# Analog_-_High_Speed_DE.net
KiCad netlist of a schematic drawn in Altium Designer
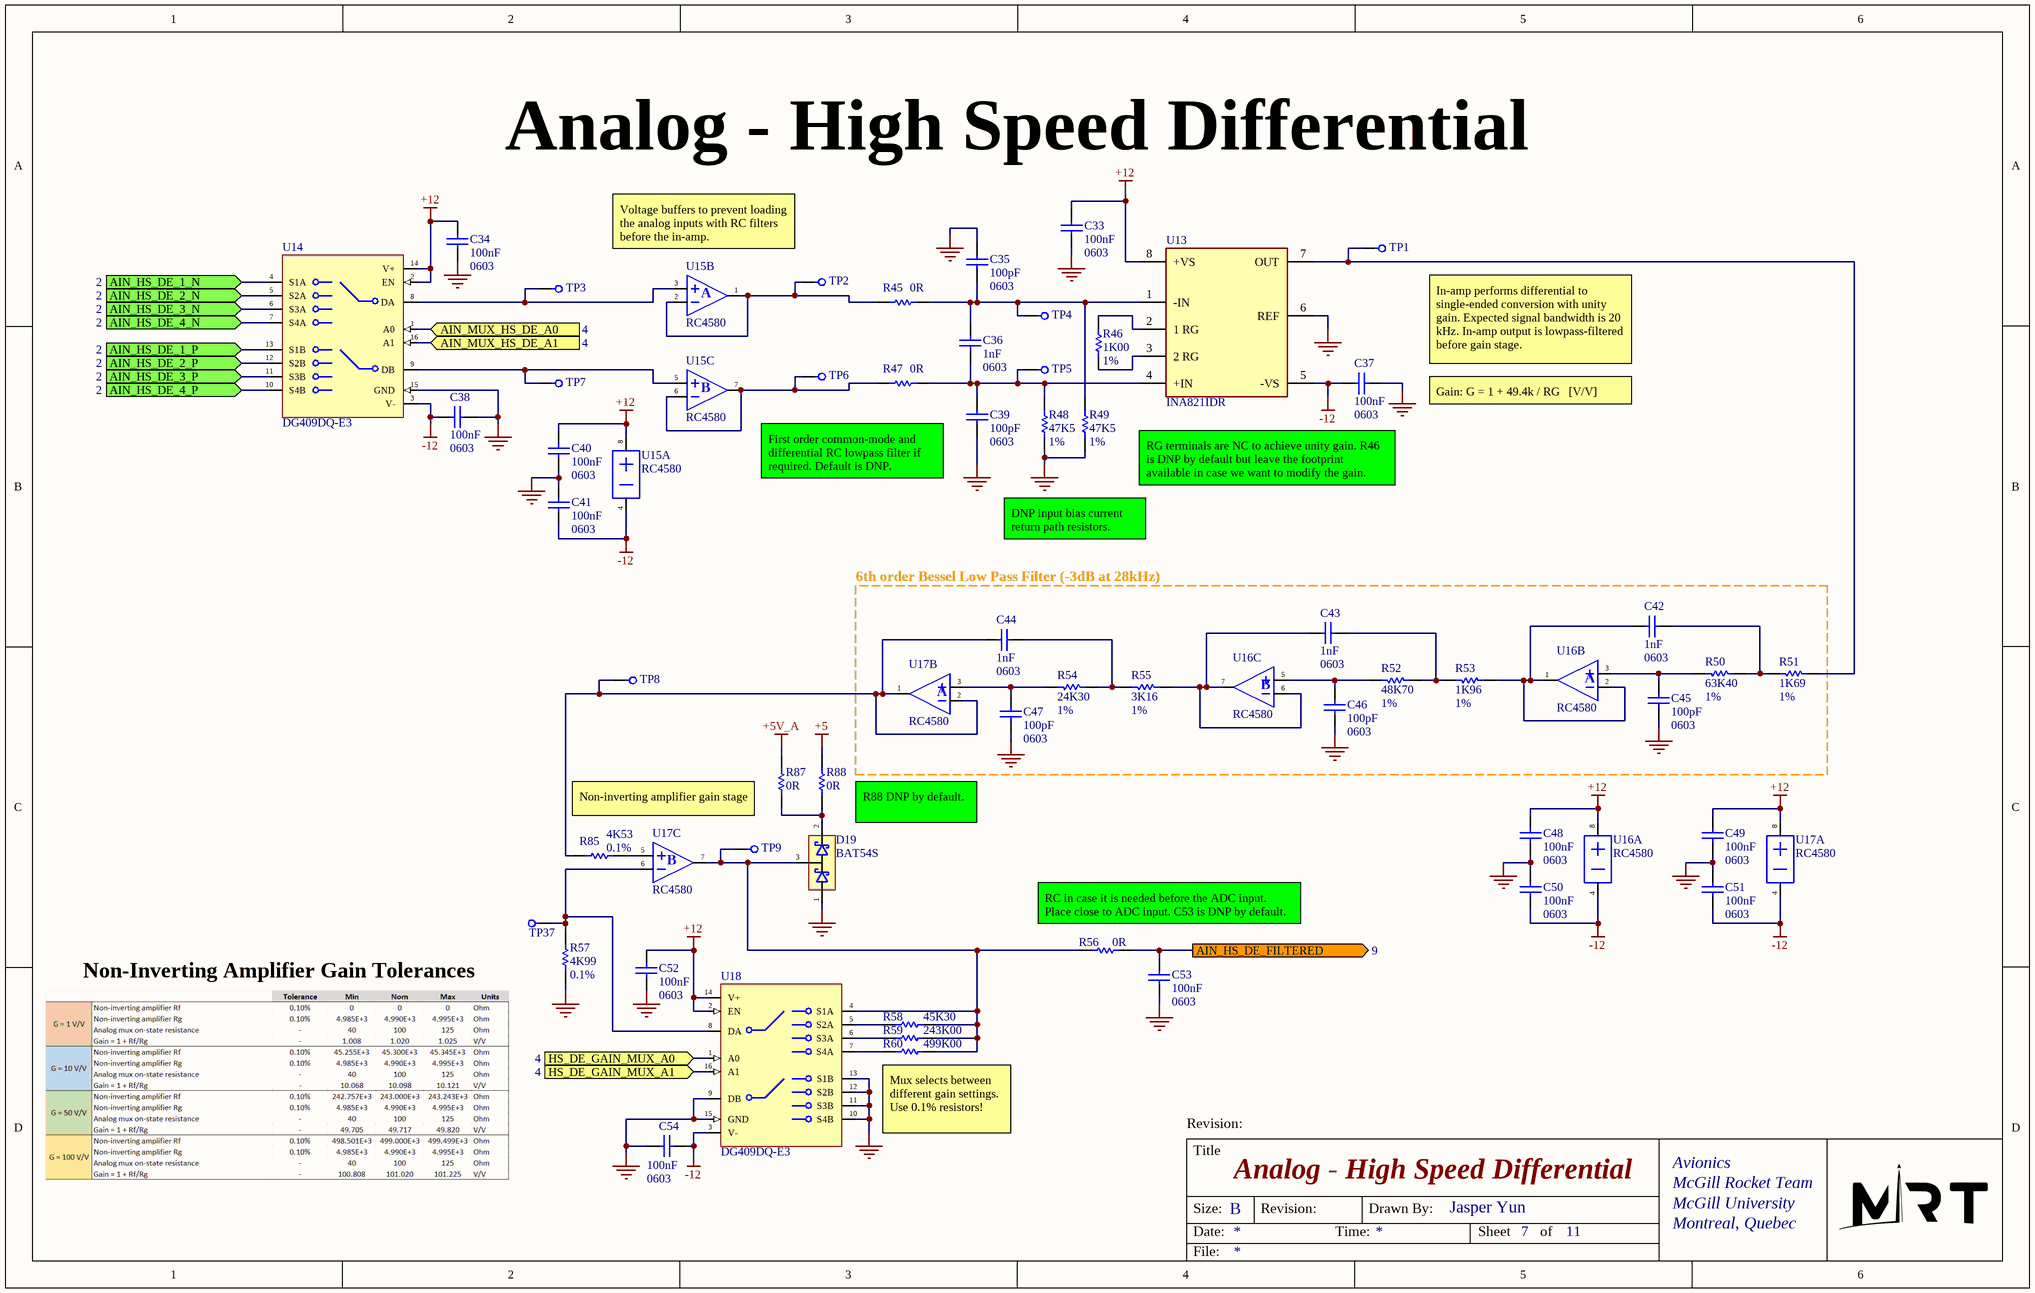
[diagram p0: Analog - High Speed DE.SchDoc]

(export (version "E")
  (design (tool "Eeschema 10.0.6"))
  (components
    (comp (ref "C33")
      (value "100nF")
      (footprint "0603 CAP SAMSUNG CL10C")
      (description "Capacitor")
      (fields (field (name "ALTIUM_VALUE") "0603") (field (name "PUBLISHER") "Altium Limited"))
      (libsource (lib "Miscellaneous Devices") (part "Cap"))
    )
    (comp (ref "C34")
      (value "100nF")
      (footprint "0603 CAP SAMSUNG CL10C")
      (description "Capacitor")
      (fields (field (name "ALTIUM_VALUE") "0603") (field (name "PUBLISHER") "Altium Limited"))
      (libsource (lib "Miscellaneous Devices") (part "Cap"))
    )
    (comp (ref "C35")
      (value "100pF")
      (footprint "0603 CAP SAMSUNG CL10C")
      (description "Capacitor")
      (fields (field (name "ALTIUM_VALUE") "0603") (field (name "PUBLISHER") "Altium Limited"))
      (libsource (lib "Miscellaneous Devices") (part "Cap"))
    )
    (comp (ref "C36")
      (value "1nF")
      (footprint "0603 CAP SAMSUNG CL10C")
      (description "Capacitor")
      (fields (field (name "ALTIUM_VALUE") "0603") (field (name "PUBLISHER") "Altium Limited"))
      (libsource (lib "Miscellaneous Devices") (part "Cap"))
    )
    (comp (ref "C37")
      (value "100nF")
      (footprint "0603 CAP SAMSUNG CL10C")
      (description "Capacitor")
      (fields (field (name "ALTIUM_VALUE") "0603") (field (name "PUBLISHER") "Altium Limited"))
      (libsource (lib "Miscellaneous Devices") (part "Cap"))
    )
    (comp (ref "C38")
      (value "100nF")
      (footprint "0603 CAP SAMSUNG CL10C")
      (description "Capacitor")
      (fields (field (name "ALTIUM_VALUE") "0603") (field (name "PUBLISHER") "Altium Limited"))
      (libsource (lib "Miscellaneous Devices") (part "Cap"))
    )
    (comp (ref "C39")
      (value "100pF")
      (footprint "0603 CAP SAMSUNG CL10C")
      (description "Capacitor")
      (fields (field (name "ALTIUM_VALUE") "0603") (field (name "PUBLISHER") "Altium Limited"))
      (libsource (lib "Miscellaneous Devices") (part "Cap"))
    )
    (comp (ref "C40")
      (value "100nF")
      (footprint "0603 CAP SAMSUNG CL10C")
      (description "Capacitor")
      (fields (field (name "ALTIUM_VALUE") "0603") (field (name "PUBLISHER") "Altium Limited"))
      (libsource (lib "Miscellaneous Devices") (part "Cap"))
    )
    (comp (ref "C41")
      (value "100nF")
      (footprint "0603 CAP SAMSUNG CL10C")
      (description "Capacitor")
      (fields (field (name "ALTIUM_VALUE") "0603") (field (name "PUBLISHER") "Altium Limited"))
      (libsource (lib "Miscellaneous Devices") (part "Cap"))
    )
    (comp (ref "C42")
      (value "1nF")
      (footprint "0603 CAP SAMSUNG CL10C")
      (description "Capacitor")
      (fields (field (name "ALTIUM_VALUE") "0603") (field (name "PUBLISHER") "Altium Limited"))
      (libsource (lib "Miscellaneous Devices") (part "Cap"))
    )
    (comp (ref "C43")
      (value "1nF")
      (footprint "0603 CAP SAMSUNG CL10C")
      (description "Capacitor")
      (fields (field (name "ALTIUM_VALUE") "0603") (field (name "PUBLISHER") "Altium Limited"))
      (libsource (lib "Miscellaneous Devices") (part "Cap"))
    )
    (comp (ref "C44")
      (value "1nF")
      (footprint "0603 CAP SAMSUNG CL10C")
      (description "Capacitor")
      (fields (field (name "ALTIUM_VALUE") "0603") (field (name "PUBLISHER") "Altium Limited"))
      (libsource (lib "Miscellaneous Devices") (part "Cap"))
    )
    (comp (ref "C45")
      (value "100pF")
      (footprint "0603 CAP SAMSUNG CL10C")
      (description "Capacitor")
      (fields (field (name "ALTIUM_VALUE") "0603") (field (name "PUBLISHER") "Altium Limited"))
      (libsource (lib "Miscellaneous Devices") (part "Cap"))
    )
    (comp (ref "C46")
      (value "100pF")
      (footprint "0603 CAP SAMSUNG CL10C")
      (description "Capacitor")
      (fields (field (name "ALTIUM_VALUE") "0603") (field (name "PUBLISHER") "Altium Limited"))
      (libsource (lib "Miscellaneous Devices") (part "Cap"))
    )
    (comp (ref "C47")
      (value "100pF")
      (footprint "0603 CAP SAMSUNG CL10C")
      (description "Capacitor")
      (fields (field (name "ALTIUM_VALUE") "0603") (field (name "PUBLISHER") "Altium Limited"))
      (libsource (lib "Miscellaneous Devices") (part "Cap"))
    )
    (comp (ref "C48")
      (value "100nF")
      (footprint "0603 CAP SAMSUNG CL10C")
      (description "Capacitor")
      (fields (field (name "ALTIUM_VALUE") "0603") (field (name "PUBLISHER") "Altium Limited"))
      (libsource (lib "Miscellaneous Devices") (part "Cap"))
    )
    (comp (ref "C49")
      (value "100nF")
      (footprint "0603 CAP SAMSUNG CL10C")
      (description "Capacitor")
      (fields (field (name "ALTIUM_VALUE") "0603") (field (name "PUBLISHER") "Altium Limited"))
      (libsource (lib "Miscellaneous Devices") (part "Cap"))
    )
    (comp (ref "C50")
      (value "100nF")
      (footprint "0603 CAP SAMSUNG CL10C")
      (description "Capacitor")
      (fields (field (name "ALTIUM_VALUE") "0603") (field (name "PUBLISHER") "Altium Limited"))
      (libsource (lib "Miscellaneous Devices") (part "Cap"))
    )
    (comp (ref "C51")
      (value "100nF")
      (footprint "0603 CAP SAMSUNG CL10C")
      (description "Capacitor")
      (fields (field (name "ALTIUM_VALUE") "0603") (field (name "PUBLISHER") "Altium Limited"))
      (libsource (lib "Miscellaneous Devices") (part "Cap"))
    )
    (comp (ref "C52")
      (value "100nF")
      (footprint "0603 CAP SAMSUNG CL10C")
      (description "Capacitor")
      (fields (field (name "ALTIUM_VALUE") "0603") (field (name "PUBLISHER") "Altium Limited"))
      (libsource (lib "Miscellaneous Devices") (part "Cap"))
    )
    (comp (ref "C53")
      (value "100nF")
      (footprint "0603 CAP SAMSUNG CL10C")
      (description "Capacitor")
      (fields (field (name "ALTIUM_VALUE") "0603") (field (name "PUBLISHER") "Altium Limited"))
      (libsource (lib "Miscellaneous Devices") (part "Cap"))
    )
    (comp (ref "C54")
      (value "100nF")
      (footprint "0603 CAP SAMSUNG CL10C")
      (description "Capacitor")
      (fields (field (name "ALTIUM_VALUE") "0603") (field (name "PUBLISHER") "Altium Limited"))
      (libsource (lib "Miscellaneous Devices") (part "Cap"))
    )
    (comp (ref "D19")
      (value "BAT54S")
      (footprint "SOT23-3")
      (description "Rectifier Diode Small Signal Schottky 40V 0.3A 5ns 3-Pin SOT-23 T/R")
      (fields
        (field (name "MANUFACTURER") "STMicroelectronics")
        (field (name "MANUFACTURER PART NUMBER") "BAT54SFILM")
      )
      (libsource (lib "MRT SCH Library") (part "Schottky Diode Array BAT54S"))
    )
    (comp (ref "R45")
      (value "0R")
      (footprint "0603 RES")
      (description "Resistor")
      (fields (field (name "PUBLISHER") "Altium Limited"))
      (libsource (lib "Miscellaneous Devices") (part "Res1"))
    )
    (comp (ref "R46")
      (value "1K00")
      (footprint "0603 RES")
      (description "Resistor")
      (fields (field (name "ALTIUM_VALUE") "1%") (field (name "PUBLISHER") "Altium Limited"))
      (libsource (lib "Miscellaneous Devices") (part "Res1"))
    )
    (comp (ref "R47")
      (value "0R")
      (footprint "0603 RES")
      (description "Resistor")
      (fields (field (name "PUBLISHER") "Altium Limited"))
      (libsource (lib "Miscellaneous Devices") (part "Res1"))
    )
    (comp (ref "R48")
      (value "47K5")
      (footprint "0603 RES")
      (description "Resistor")
      (fields (field (name "ALTIUM_VALUE") "1%") (field (name "PUBLISHER") "Altium Limited"))
      (libsource (lib "Miscellaneous Devices") (part "Res1"))
    )
    (comp (ref "R49")
      (value "47K5")
      (footprint "0603 RES")
      (description "Resistor")
      (fields (field (name "ALTIUM_VALUE") "1%") (field (name "PUBLISHER") "Altium Limited"))
      (libsource (lib "Miscellaneous Devices") (part "Res1"))
    )
    (comp (ref "R50")
      (value "63K40")
      (footprint "0603 RES")
      (description "Resistor")
      (fields (field (name "ALTIUM_VALUE") "1%") (field (name "PUBLISHER") "Altium Limited"))
      (libsource (lib "Miscellaneous Devices") (part "Res1"))
    )
    (comp (ref "R51")
      (value "1K69")
      (footprint "0603 RES")
      (description "Resistor")
      (fields (field (name "ALTIUM_VALUE") "1%") (field (name "PUBLISHER") "Altium Limited"))
      (libsource (lib "Miscellaneous Devices") (part "Res1"))
    )
    (comp (ref "R52")
      (value "48K70")
      (footprint "0603 RES")
      (description "Resistor")
      (fields (field (name "ALTIUM_VALUE") "1%") (field (name "PUBLISHER") "Altium Limited"))
      (libsource (lib "Miscellaneous Devices") (part "Res1"))
    )
    (comp (ref "R53")
      (value "1K96")
      (footprint "0603 RES")
      (description "Resistor")
      (fields (field (name "ALTIUM_VALUE") "1%") (field (name "PUBLISHER") "Altium Limited"))
      (libsource (lib "Miscellaneous Devices") (part "Res1"))
    )
    (comp (ref "R54")
      (value "24K30")
      (footprint "0603 RES")
      (description "Resistor")
      (fields (field (name "ALTIUM_VALUE") "1%") (field (name "PUBLISHER") "Altium Limited"))
      (libsource (lib "Miscellaneous Devices") (part "Res1"))
    )
    (comp (ref "R55")
      (value "3K16")
      (footprint "0603 RES")
      (description "Resistor")
      (fields (field (name "ALTIUM_VALUE") "1%") (field (name "PUBLISHER") "Altium Limited"))
      (libsource (lib "Miscellaneous Devices") (part "Res1"))
    )
    (comp (ref "R56")
      (value "0R")
      (footprint "0603 RES")
      (description "Resistor")
      (fields (field (name "PUBLISHER") "Altium Limited"))
      (libsource (lib "Miscellaneous Devices") (part "Res1"))
    )
    (comp (ref "R57")
      (value "4K99")
      (footprint "0603 RES")
      (description "Resistor")
      (fields (field (name "ALTIUM_VALUE") "0.1%") (field (name "PUBLISHER") "Altium Limited"))
      (libsource (lib "Miscellaneous Devices") (part "Res1"))
    )
    (comp (ref "R58")
      (value "45K30")
      (footprint "0603 RES")
      (description "Resistor")
      (fields (field (name "PUBLISHER") "Altium Limited"))
      (libsource (lib "Miscellaneous Devices") (part "Res1"))
    )
    (comp (ref "R59")
      (value "243K00")
      (footprint "0603 RES")
      (description "Resistor")
      (fields (field (name "PUBLISHER") "Altium Limited"))
      (libsource (lib "Miscellaneous Devices") (part "Res1"))
    )
    (comp (ref "R60")
      (value "499K00")
      (footprint "0603 RES")
      (description "Resistor")
      (fields (field (name "PUBLISHER") "Altium Limited"))
      (libsource (lib "Miscellaneous Devices") (part "Res1"))
    )
    (comp (ref "R85")
      (value "4K53")
      (footprint "0603 RES")
      (description "Resistor")
      (fields (field (name "ALTIUM_VALUE") "0.1%") (field (name "PUBLISHER") "Altium Limited"))
      (libsource (lib "Miscellaneous Devices") (part "Res1"))
    )
    (comp (ref "R87")
      (value "0R")
      (footprint "0603 RES")
      (description "Resistor")
      (fields (field (name "PUBLISHER") "Altium Limited"))
      (libsource (lib "Miscellaneous Devices") (part "Res1"))
    )
    (comp (ref "R88")
      (value "0R")
      (footprint "0603 RES")
      (description "Resistor")
      (fields (field (name "PUBLISHER") "Altium Limited"))
      (libsource (lib "Miscellaneous Devices") (part "Res1"))
    )
    (comp (ref "TP1")
      (value "Test Point")
      (footprint "Test Point Keystone 5015")
      (description "Keystone 5015 Test point")
      (libsource (lib "MRT SCH Library") (part "Test Point"))
    )
    (comp (ref "TP2")
      (value "Test Point")
      (footprint "TEST POINT SMD PAD")
      (description "Keystone 5015 Test point")
      (libsource (lib "MRT SCH Library") (part "Test Point"))
    )
    (comp (ref "TP3")
      (value "Test Point")
      (footprint "TEST POINT SMD PAD")
      (description "Keystone 5015 Test point")
      (libsource (lib "MRT SCH Library") (part "Test Point"))
    )
    (comp (ref "TP4")
      (value "Test Point")
      (footprint "TEST POINT SMD PAD")
      (description "Keystone 5015 Test point")
      (libsource (lib "MRT SCH Library") (part "Test Point"))
    )
    (comp (ref "TP5")
      (value "Test Point")
      (footprint "TEST POINT SMD PAD")
      (description "Keystone 5015 Test point")
      (libsource (lib "MRT SCH Library") (part "Test Point"))
    )
    (comp (ref "TP6")
      (value "Test Point")
      (footprint "TEST POINT SMD PAD")
      (description "Keystone 5015 Test point")
      (libsource (lib "MRT SCH Library") (part "Test Point"))
    )
    (comp (ref "TP7")
      (value "Test Point")
      (footprint "TEST POINT SMD PAD")
      (description "Keystone 5015 Test point")
      (libsource (lib "MRT SCH Library") (part "Test Point"))
    )
    (comp (ref "TP8")
      (value "Test Point")
      (footprint "Test Point Keystone 5015")
      (description "Keystone 5015 Test point")
      (libsource (lib "MRT SCH Library") (part "Test Point"))
    )
    (comp (ref "TP9")
      (value "Test Point")
      (footprint "Test Point Keystone 5015")
      (description "Keystone 5015 Test point")
      (libsource (lib "MRT SCH Library") (part "Test Point"))
    )
    (comp (ref "TP37")
      (value "Test Point")
      (footprint "Test Point Keystone 5015")
      (description "Keystone 5015 Test point")
      (libsource (lib "MRT SCH Library") (part "Test Point"))
    )
    (comp (ref "U13")
      (value "INA821IDR")
      (footprint "FP-D0008A-IPC_A")
      (description "IC INST AMP 1 CIRCUIT 8SOIC")
      (libsource (lib "Altium Content Vault") (part "f8dea4e880bbf27f1efc339ce0e0823"))
    )
    (comp (ref "U14")
      (value "DG409DQ-E3")
      (footprint "TSSOP-16")
      (description "DG409 Series 20 V 8-Ch/Dual 4-Ch High-Performance CMOS Analog Multiplexer")
      (fields (field (name "MANUFACTURER") "Vishay Siliconix"))
      (libsource (lib "") (part "Analog Mux DG409DQ-E3_1"))
    )
    (comp (ref "U15")
      (value "RC4580")
      (footprint "SOIC-8")
      (fields
        (field (name "MANUFACTURER") "Texas Instruments")
        (field (name "MANUFACTURER PART NUMBER") "RC4580IDR")
      )
      (libsource (lib "MRT SCH Library") (part "OP AMP RC4580"))
    )
    (comp (ref "U16")
      (value "RC4580")
      (footprint "SOIC-8")
      (fields
        (field (name "MANUFACTURER") "Texas Instruments")
        (field (name "MANUFACTURER PART NUMBER") "RC4580IDR")
      )
      (libsource (lib "MRT SCH Library") (part "OP AMP RC4580"))
    )
    (comp (ref "U17")
      (value "RC4580")
      (footprint "SOIC-8")
      (fields
        (field (name "MANUFACTURER") "Texas Instruments")
        (field (name "MANUFACTURER PART NUMBER") "RC4580IDR")
      )
      (libsource (lib "MRT SCH Library") (part "OP AMP RC4580"))
    )
    (comp (ref "U18")
      (value "DG409DQ-E3")
      (footprint "TSSOP-16")
      (description "DG409 Series 20 V 8-Ch/Dual 4-Ch High-Performance CMOS Analog Multiplexer")
      (fields (field (name "MANUFACTURER") "Vishay Siliconix"))
      (libsource (lib "MRT SCH Library") (part "Analog Mux DG409DQ-E3"))
    )
  )
  (nets
    (net (code "1") (name "+5") (class "Default")
      (node (ref "R88") (pin "1") (pinfunction "1_1") (pintype "passive"))
    )
    (net (code "2") (name "+5V_A") (class "Default")
      (node (ref "R87") (pin "1") (pinfunction "1_1") (pintype "passive"))
    )
    (net (code "3") (name "+12") (class "Default")
      (node (ref "C33") (pin "2") (pinfunction "2_2") (pintype "passive"))
      (node (ref "C34") (pin "2") (pinfunction "2_2") (pintype "passive"))
      (node (ref "C40") (pin "2") (pinfunction "2_2") (pintype "passive"))
      (node (ref "C48") (pin "2") (pinfunction "2_2") (pintype "passive"))
      (node (ref "C49") (pin "2") (pinfunction "2_2") (pintype "passive"))
      (node (ref "C52") (pin "2") (pinfunction "2_2") (pintype "passive"))
      (node (ref "U13") (pin "8") (pinfunction "+VS_8") (pintype "power_in"))
      (node (ref "U14") (pin "14") (pinfunction "V+_14") (pintype "passive"))
      (node (ref "U14") (pin "2") (pinfunction "EN_2") (pintype "input"))
      (node (ref "U15") (pin "8") (pinfunction "VCC+_8") (pintype "passive"))
      (node (ref "U16") (pin "8") (pinfunction "VCC+_8") (pintype "passive"))
      (node (ref "U17") (pin "8") (pinfunction "VCC+_8") (pintype "passive"))
      (node (ref "U18") (pin "14") (pinfunction "V+_14") (pintype "passive"))
      (node (ref "U18") (pin "2") (pinfunction "EN_2") (pintype "input"))
    )
    (net (code "4") (name "-12") (class "Default")
      (node (ref "C37") (pin "2") (pinfunction "2_2") (pintype "passive"))
      (node (ref "C38") (pin "2") (pinfunction "2_2") (pintype "passive"))
      (node (ref "C41") (pin "1") (pinfunction "1_1") (pintype "passive"))
      (node (ref "C50") (pin "1") (pinfunction "1_1") (pintype "passive"))
      (node (ref "C51") (pin "1") (pinfunction "1_1") (pintype "passive"))
      (node (ref "C54") (pin "2") (pinfunction "2_2") (pintype "passive"))
      (node (ref "U13") (pin "5") (pinfunction "-VS_5") (pintype "power_in"))
      (node (ref "U14") (pin "3") (pinfunction "V-_3") (pintype "passive"))
      (node (ref "U15") (pin "4") (pinfunction "VCC-_4") (pintype "passive"))
      (node (ref "U16") (pin "4") (pinfunction "VCC-_4") (pintype "passive"))
      (node (ref "U17") (pin "4") (pinfunction "VCC-_4") (pintype "passive"))
      (node (ref "U18") (pin "3") (pinfunction "V-_3") (pintype "passive"))
    )
    (net (code "5") (name "/AIN_HS_DE_1_N") (class "Default")
      (node (ref "U14") (pin "4") (pinfunction "S1A_4") (pintype "passive"))
    )
    (net (code "6") (name "/AIN_HS_DE_1_P") (class "Default")
      (node (ref "U14") (pin "13") (pinfunction "S1B_13") (pintype "passive"))
    )
    (net (code "7") (name "/AIN_HS_DE_2_N") (class "Default")
      (node (ref "U14") (pin "5") (pinfunction "S2A_5") (pintype "passive"))
    )
    (net (code "8") (name "/AIN_HS_DE_2_P") (class "Default")
      (node (ref "U14") (pin "12") (pinfunction "S2B_12") (pintype "passive"))
    )
    (net (code "9") (name "/AIN_HS_DE_3_N") (class "Default")
      (node (ref "U14") (pin "6") (pinfunction "S3A_6") (pintype "passive"))
    )
    (net (code "10") (name "/AIN_HS_DE_3_P") (class "Default")
      (node (ref "U14") (pin "11") (pinfunction "S3B_11") (pintype "passive"))
    )
    (net (code "11") (name "/AIN_HS_DE_4_N") (class "Default")
      (node (ref "U14") (pin "7") (pinfunction "S4A_7") (pintype "passive"))
    )
    (net (code "12") (name "/AIN_HS_DE_4_P") (class "Default")
      (node (ref "U14") (pin "10") (pinfunction "S4B_10") (pintype "passive"))
    )
    (net (code "13") (name "/AIN_HS_DE_FILTERED") (class "Default")
      (node (ref "C53") (pin "2") (pinfunction "2_2") (pintype "passive"))
      (node (ref "R56") (pin "1") (pinfunction "1_1") (pintype "passive"))
    )
    (net (code "14") (name "/AIN_MUX_HS_DE_A0") (class "Default")
      (node (ref "U14") (pin "1") (pinfunction "A0_1") (pintype "input"))
    )
    (net (code "15") (name "/AIN_MUX_HS_DE_A1") (class "Default")
      (node (ref "U14") (pin "16") (pinfunction "A1_16") (pintype "input"))
    )
    (net (code "16") (name "/HS_DE_GAIN_MUX_A0") (class "Default")
      (node (ref "U18") (pin "1") (pinfunction "A0_1") (pintype "input"))
    )
    (net (code "17") (name "/HS_DE_GAIN_MUX_A1") (class "Default")
      (node (ref "U18") (pin "16") (pinfunction "A1_16") (pintype "input"))
    )
    (net (code "18") (name "GND") (class "Default")
      (node (ref "C33") (pin "1") (pinfunction "1_1") (pintype "passive"))
      (node (ref "C34") (pin "1") (pinfunction "1_1") (pintype "passive"))
      (node (ref "C35") (pin "2") (pinfunction "2_2") (pintype "passive"))
      (node (ref "C37") (pin "1") (pinfunction "1_1") (pintype "passive"))
      (node (ref "C38") (pin "1") (pinfunction "1_1") (pintype "passive"))
      (node (ref "C39") (pin "1") (pinfunction "1_1") (pintype "passive"))
      (node (ref "C40") (pin "1") (pinfunction "1_1") (pintype "passive"))
      (node (ref "C41") (pin "2") (pinfunction "2_2") (pintype "passive"))
      (node (ref "C45") (pin "1") (pinfunction "1_1") (pintype "passive"))
      (node (ref "C46") (pin "1") (pinfunction "1_1") (pintype "passive"))
      (node (ref "C47") (pin "1") (pinfunction "1_1") (pintype "passive"))
      (node (ref "C48") (pin "1") (pinfunction "1_1") (pintype "passive"))
      (node (ref "C49") (pin "1") (pinfunction "1_1") (pintype "passive"))
      (node (ref "C50") (pin "2") (pinfunction "2_2") (pintype "passive"))
      (node (ref "C51") (pin "2") (pinfunction "2_2") (pintype "passive"))
      (node (ref "C52") (pin "1") (pinfunction "1_1") (pintype "passive"))
      (node (ref "C53") (pin "1") (pinfunction "1_1") (pintype "passive"))
      (node (ref "C54") (pin "1") (pinfunction "1_1") (pintype "passive"))
      (node (ref "D19") (pin "1") (pinfunction "1_1") (pintype "passive"))
      (node (ref "R48") (pin "1") (pinfunction "1_1") (pintype "passive"))
      (node (ref "R49") (pin "1") (pinfunction "1_1") (pintype "passive"))
      (node (ref "R57") (pin "1") (pinfunction "1_1") (pintype "passive"))
      (node (ref "U13") (pin "6") (pinfunction "REF_6") (pintype "passive"))
      (node (ref "U14") (pin "15") (pinfunction "GND_15") (pintype "input"))
      (node (ref "U18") (pin "10") (pinfunction "S4B_10") (pintype "passive"))
      (node (ref "U18") (pin "11") (pinfunction "S3B_11") (pintype "passive"))
      (node (ref "U18") (pin "12") (pinfunction "S2B_12") (pintype "passive"))
      (node (ref "U18") (pin "13") (pinfunction "S1B_13") (pintype "passive"))
      (node (ref "U18") (pin "15") (pinfunction "GND_15") (pintype "input"))
      (node (ref "U18") (pin "9") (pinfunction "DB_9") (pintype "passive"))
    )
    (net (code "19") (name "Net-(C42-Pad1)") (class "Default")
      (node (ref "C42") (pin "1") (pinfunction "1_1") (pintype "passive"))
      (node (ref "R53") (pin "1") (pinfunction "1_1") (pintype "passive"))
      (node (ref "U16") (pin "1") (pinfunction "1_1") (pintype "passive"))
      (node (ref "U16") (pin "2") (pinfunction "2_2") (pintype "passive"))
    )
    (net (code "20") (name "Net-(C42-Pad2)") (class "Default")
      (node (ref "C42") (pin "2") (pinfunction "2_2") (pintype "passive"))
      (node (ref "R50") (pin "1") (pinfunction "1_1") (pintype "passive"))
      (node (ref "R51") (pin "2") (pinfunction "2_2") (pintype "passive"))
    )
    (net (code "21") (name "Net-(C43-Pad1)") (class "Default")
      (node (ref "C43") (pin "1") (pinfunction "1_1") (pintype "passive"))
      (node (ref "R55") (pin "1") (pinfunction "1_1") (pintype "passive"))
      (node (ref "U16") (pin "6") (pinfunction "6_6") (pintype "passive"))
      (node (ref "U16") (pin "7") (pinfunction "7_7") (pintype "passive"))
    )
    (net (code "22") (name "Net-(C43-Pad2)") (class "Default")
      (node (ref "C43") (pin "2") (pinfunction "2_2") (pintype "passive"))
      (node (ref "R52") (pin "1") (pinfunction "1_1") (pintype "passive"))
      (node (ref "R53") (pin "2") (pinfunction "2_2") (pintype "passive"))
    )
    (net (code "23") (name "Net-(C44-Pad1)") (class "Default")
      (node (ref "C44") (pin "1") (pinfunction "1_1") (pintype "passive"))
      (node (ref "R85") (pin "2") (pinfunction "2_2") (pintype "passive"))
      (node (ref "TP8") (pin "1") (pinfunction "1_1") (pintype "passive"))
      (node (ref "U17") (pin "1") (pinfunction "1_1") (pintype "passive"))
      (node (ref "U17") (pin "2") (pinfunction "2_2") (pintype "passive"))
    )
    (net (code "24") (name "Net-(C44-Pad2)") (class "Default")
      (node (ref "C44") (pin "2") (pinfunction "2_2") (pintype "passive"))
      (node (ref "R54") (pin "1") (pinfunction "1_1") (pintype "passive"))
      (node (ref "R55") (pin "2") (pinfunction "2_2") (pintype "passive"))
    )
    (net (code "25") (name "Net-(C45-Pad2)") (class "Default")
      (node (ref "C45") (pin "2") (pinfunction "2_2") (pintype "passive"))
      (node (ref "R50") (pin "2") (pinfunction "2_2") (pintype "passive"))
      (node (ref "U16") (pin "3") (pinfunction "3_3") (pintype "passive"))
    )
    (net (code "26") (name "Net-(C46-Pad2)") (class "Default")
      (node (ref "C46") (pin "2") (pinfunction "2_2") (pintype "passive"))
      (node (ref "R52") (pin "2") (pinfunction "2_2") (pintype "passive"))
      (node (ref "U16") (pin "5") (pinfunction "5_5") (pintype "passive"))
    )
    (net (code "27") (name "Net-(C47-Pad2)") (class "Default")
      (node (ref "C47") (pin "2") (pinfunction "2_2") (pintype "passive"))
      (node (ref "R54") (pin "2") (pinfunction "2_2") (pintype "passive"))
      (node (ref "U17") (pin "3") (pinfunction "3_3") (pintype "passive"))
    )
    (net (code "28") (name "Net-(D19-Pad2)") (class "Default")
      (node (ref "D19") (pin "2") (pinfunction "2_2") (pintype "passive"))
      (node (ref "R87") (pin "2") (pinfunction "2_2") (pintype "passive"))
      (node (ref "R88") (pin "2") (pinfunction "2_2") (pintype "passive"))
    )
    (net (code "29") (name "Net-(R45-Pad2)") (class "Default")
      (node (ref "R45") (pin "2") (pinfunction "2_2") (pintype "passive"))
      (node (ref "TP2") (pin "1") (pinfunction "1_1") (pintype "passive"))
      (node (ref "U15") (pin "1") (pinfunction "1_1") (pintype "passive"))
      (node (ref "U15") (pin "2") (pinfunction "2_2") (pintype "passive"))
    )
    (net (code "30") (name "Net-(R47-Pad2)") (class "Default")
      (node (ref "R47") (pin "2") (pinfunction "2_2") (pintype "passive"))
      (node (ref "TP6") (pin "1") (pinfunction "1_1") (pintype "passive"))
      (node (ref "U15") (pin "6") (pinfunction "6_6") (pintype "passive"))
      (node (ref "U15") (pin "7") (pinfunction "7_7") (pintype "passive"))
    )
    (net (code "31") (name "Net-(R85-Pad1)") (class "Default")
      (node (ref "R85") (pin "1") (pinfunction "1_1") (pintype "passive"))
      (node (ref "U17") (pin "5") (pinfunction "5_5") (pintype "passive"))
    )
    (net (code "32") (name "Net-(U13-+IN)") (class "Default")
      (node (ref "C36") (pin "1") (pinfunction "1_1") (pintype "passive"))
      (node (ref "C39") (pin "2") (pinfunction "2_2") (pintype "passive"))
      (node (ref "R47") (pin "1") (pinfunction "1_1") (pintype "passive"))
      (node (ref "R48") (pin "2") (pinfunction "2_2") (pintype "passive"))
      (node (ref "TP5") (pin "1") (pinfunction "1_1") (pintype "passive"))
      (node (ref "U13") (pin "4") (pinfunction "+IN_4") (pintype "tri_state"))
    )
    (net (code "33") (name "Net-(U13--IN)") (class "Default")
      (node (ref "C35") (pin "1") (pinfunction "1_1") (pintype "passive"))
      (node (ref "C36") (pin "2") (pinfunction "2_2") (pintype "passive"))
      (node (ref "R45") (pin "1") (pinfunction "1_1") (pintype "passive"))
      (node (ref "R49") (pin "2") (pinfunction "2_2") (pintype "passive"))
      (node (ref "TP4") (pin "1") (pinfunction "1_1") (pintype "passive"))
      (node (ref "U13") (pin "1") (pinfunction "-IN_1") (pintype "tri_state"))
    )
    (net (code "34") (name "Net-(U13-1_RG)") (class "Default")
      (node (ref "R46") (pin "2") (pinfunction "2_2") (pintype "passive"))
      (node (ref "U13") (pin "2") (pinfunction "1_RG_2") (pintype "passive"))
    )
    (net (code "35") (name "Net-(U13-2_RG)") (class "Default")
      (node (ref "R46") (pin "1") (pinfunction "1_1") (pintype "passive"))
      (node (ref "U13") (pin "3") (pinfunction "2_RG_3") (pintype "passive"))
    )
    (net (code "36") (name "Net-(U13-OUT)") (class "Default")
      (node (ref "R51") (pin "1") (pinfunction "1_1") (pintype "passive"))
      (node (ref "TP1") (pin "1") (pinfunction "1_1") (pintype "passive"))
      (node (ref "U13") (pin "7") (pinfunction "OUT_7") (pintype "passive"))
    )
    (net (code "37") (name "Net-(U14-DA)") (class "Default")
      (node (ref "TP3") (pin "1") (pinfunction "1_1") (pintype "passive"))
      (node (ref "U14") (pin "8") (pinfunction "DA_8") (pintype "passive"))
      (node (ref "U15") (pin "3") (pinfunction "3_3") (pintype "passive"))
    )
    (net (code "38") (name "Net-(U14-DB)") (class "Default")
      (node (ref "TP7") (pin "1") (pinfunction "1_1") (pintype "passive"))
      (node (ref "U14") (pin "9") (pinfunction "DB_9") (pintype "passive"))
      (node (ref "U15") (pin "5") (pinfunction "5_5") (pintype "passive"))
    )
    (net (code "39") (name "Net-(U18-DA)") (class "Default")
      (node (ref "R57") (pin "2") (pinfunction "2_2") (pintype "passive"))
      (node (ref "TP37") (pin "1") (pinfunction "1_1") (pintype "passive"))
      (node (ref "U17") (pin "6") (pinfunction "6_6") (pintype "passive"))
      (node (ref "U18") (pin "8") (pinfunction "DA_8") (pintype "passive"))
    )
    (net (code "40") (name "Net-(U18-S1A)") (class "Default")
      (node (ref "D19") (pin "3") (pinfunction "3_3") (pintype "passive"))
      (node (ref "R56") (pin "2") (pinfunction "2_2") (pintype "passive"))
      (node (ref "R58") (pin "1") (pinfunction "1_1") (pintype "passive"))
      (node (ref "R59") (pin "1") (pinfunction "1_1") (pintype "passive"))
      (node (ref "R60") (pin "1") (pinfunction "1_1") (pintype "passive"))
      (node (ref "TP9") (pin "1") (pinfunction "1_1") (pintype "passive"))
      (node (ref "U17") (pin "7") (pinfunction "7_7") (pintype "passive"))
      (node (ref "U18") (pin "4") (pinfunction "S1A_4") (pintype "passive"))
    )
    (net (code "41") (name "Net-(U18-S2A)") (class "Default")
      (node (ref "R58") (pin "2") (pinfunction "2_2") (pintype "passive"))
      (node (ref "U18") (pin "5") (pinfunction "S2A_5") (pintype "passive"))
    )
    (net (code "42") (name "Net-(U18-S3A)") (class "Default")
      (node (ref "R59") (pin "2") (pinfunction "2_2") (pintype "passive"))
      (node (ref "U18") (pin "6") (pinfunction "S3A_6") (pintype "passive"))
    )
    (net (code "43") (name "Net-(U18-S4A)") (class "Default")
      (node (ref "R60") (pin "2") (pinfunction "2_2") (pintype "passive"))
      (node (ref "U18") (pin "7") (pinfunction "S4A_7") (pintype "passive"))
    )
  )
)
